# IOborad1.net
KiCad netlist of a schematic drawn in EAGLE
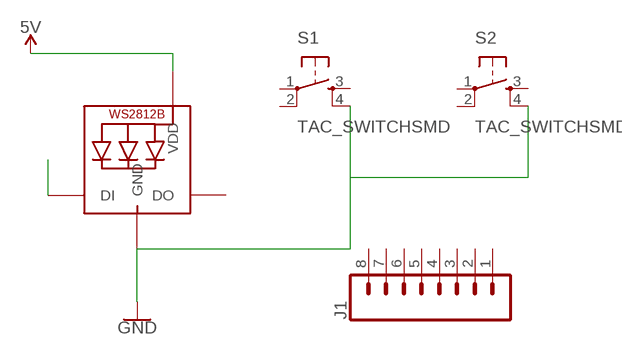
[diagram p0: schematic, sheet 1]

(export (version "E")
  (design (tool "Eeschema 10.0.6"))
  (components
    (comp (ref "J1")
      (value "CONN_08\"")
      (footprint "eagle-import:1X08")
      (libsource (lib "eagle-import") (part "CONN_08{dblquote}"))
    )
    (comp (ref "LED1")
      (value "WS2812B5050")
      (footprint "eagle-import:WS2812B")
      (libsource (lib "eagle-import") (part "WS2812B5050"))
    )
    (comp (ref "S1")
      (value "TAC_SWITCHSMD")
      (footprint "eagle-import:TACTILE-SWITCH-SMD")
      (libsource (lib "eagle-import") (part "TAC_SWITCHSMD"))
    )
    (comp (ref "S2")
      (value "TAC_SWITCHSMD")
      (footprint "eagle-import:TACTILE-SWITCH-SMD")
      (libsource (lib "eagle-import") (part "TAC_SWITCHSMD"))
    )
  )
  (nets
    (net (code "1") (name "5V") (class "Default")
      (node (ref "LED1") (pin "1-VDD") (pinfunction "VDD_1-VDD") (pintype "power_in"))
    )
    (net (code "2") (name "GND") (class "Default")
      (node (ref "LED1") (pin "3-GND") (pinfunction "GND_3-GND") (pintype "power_in"))
      (node (ref "S1") (pin "4") (pinfunction "4_4") (pintype "passive"))
      (node (ref "S2") (pin "4") (pinfunction "4_4") (pintype "passive"))
    )
    (net (code "3") (name "unconnected-(J1-Pad1)") (class "Default")
      (node (ref "J1") (pin "1") (pinfunction "1_1") (pintype "passive"))
    )
    (net (code "4") (name "unconnected-(J1-Pad2)") (class "Default")
      (node (ref "J1") (pin "2") (pinfunction "2_2") (pintype "passive"))
    )
    (net (code "5") (name "unconnected-(J1-Pad3)") (class "Default")
      (node (ref "J1") (pin "3") (pinfunction "3_3") (pintype "passive"))
    )
    (net (code "6") (name "unconnected-(J1-Pad4)") (class "Default")
      (node (ref "J1") (pin "4") (pinfunction "4_4") (pintype "passive"))
    )
    (net (code "7") (name "unconnected-(J1-Pad5)") (class "Default")
      (node (ref "J1") (pin "5") (pinfunction "5_5") (pintype "passive"))
    )
    (net (code "8") (name "unconnected-(J1-Pad6)") (class "Default")
      (node (ref "J1") (pin "6") (pinfunction "6_6") (pintype "passive"))
    )
    (net (code "9") (name "unconnected-(J1-Pad7)") (class "Default")
      (node (ref "J1") (pin "7") (pinfunction "7_7") (pintype "passive"))
    )
    (net (code "10") (name "unconnected-(J1-Pad8)") (class "Default")
      (node (ref "J1") (pin "8") (pinfunction "8_8") (pintype "passive"))
    )
    (net (code "11") (name "unconnected-(LED1-DI-Pad4-DIN)") (class "Default")
      (node (ref "LED1") (pin "4-DIN") (pinfunction "DI_4-DIN") (pintype "input"))
    )
    (net (code "12") (name "unconnected-(LED1-DO-Pad2-DOUT)") (class "Default")
      (node (ref "LED1") (pin "2-DOUT") (pinfunction "DO_2-DOUT") (pintype "output"))
    )
    (net (code "13") (name "unconnected-(S1-Pad1)") (class "Default")
      (node (ref "S1") (pin "1") (pinfunction "1_1") (pintype "passive"))
    )
    (net (code "14") (name "unconnected-(S1-Pad2)") (class "Default")
      (node (ref "S1") (pin "2") (pinfunction "2_2") (pintype "passive"))
    )
    (net (code "15") (name "unconnected-(S1-Pad3)") (class "Default")
      (node (ref "S1") (pin "3") (pinfunction "3_3") (pintype "passive"))
    )
    (net (code "16") (name "unconnected-(S2-Pad1)") (class "Default")
      (node (ref "S2") (pin "1") (pinfunction "1_1") (pintype "passive"))
    )
    (net (code "17") (name "unconnected-(S2-Pad2)") (class "Default")
      (node (ref "S2") (pin "2") (pinfunction "2_2") (pintype "passive"))
    )
    (net (code "18") (name "unconnected-(S2-Pad3)") (class "Default")
      (node (ref "S2") (pin "3") (pinfunction "3_3") (pintype "passive"))
    )
  )
)
